# fpga-bank3-outside.net
KiCad netlist of a schematic drawn in Altium Designer
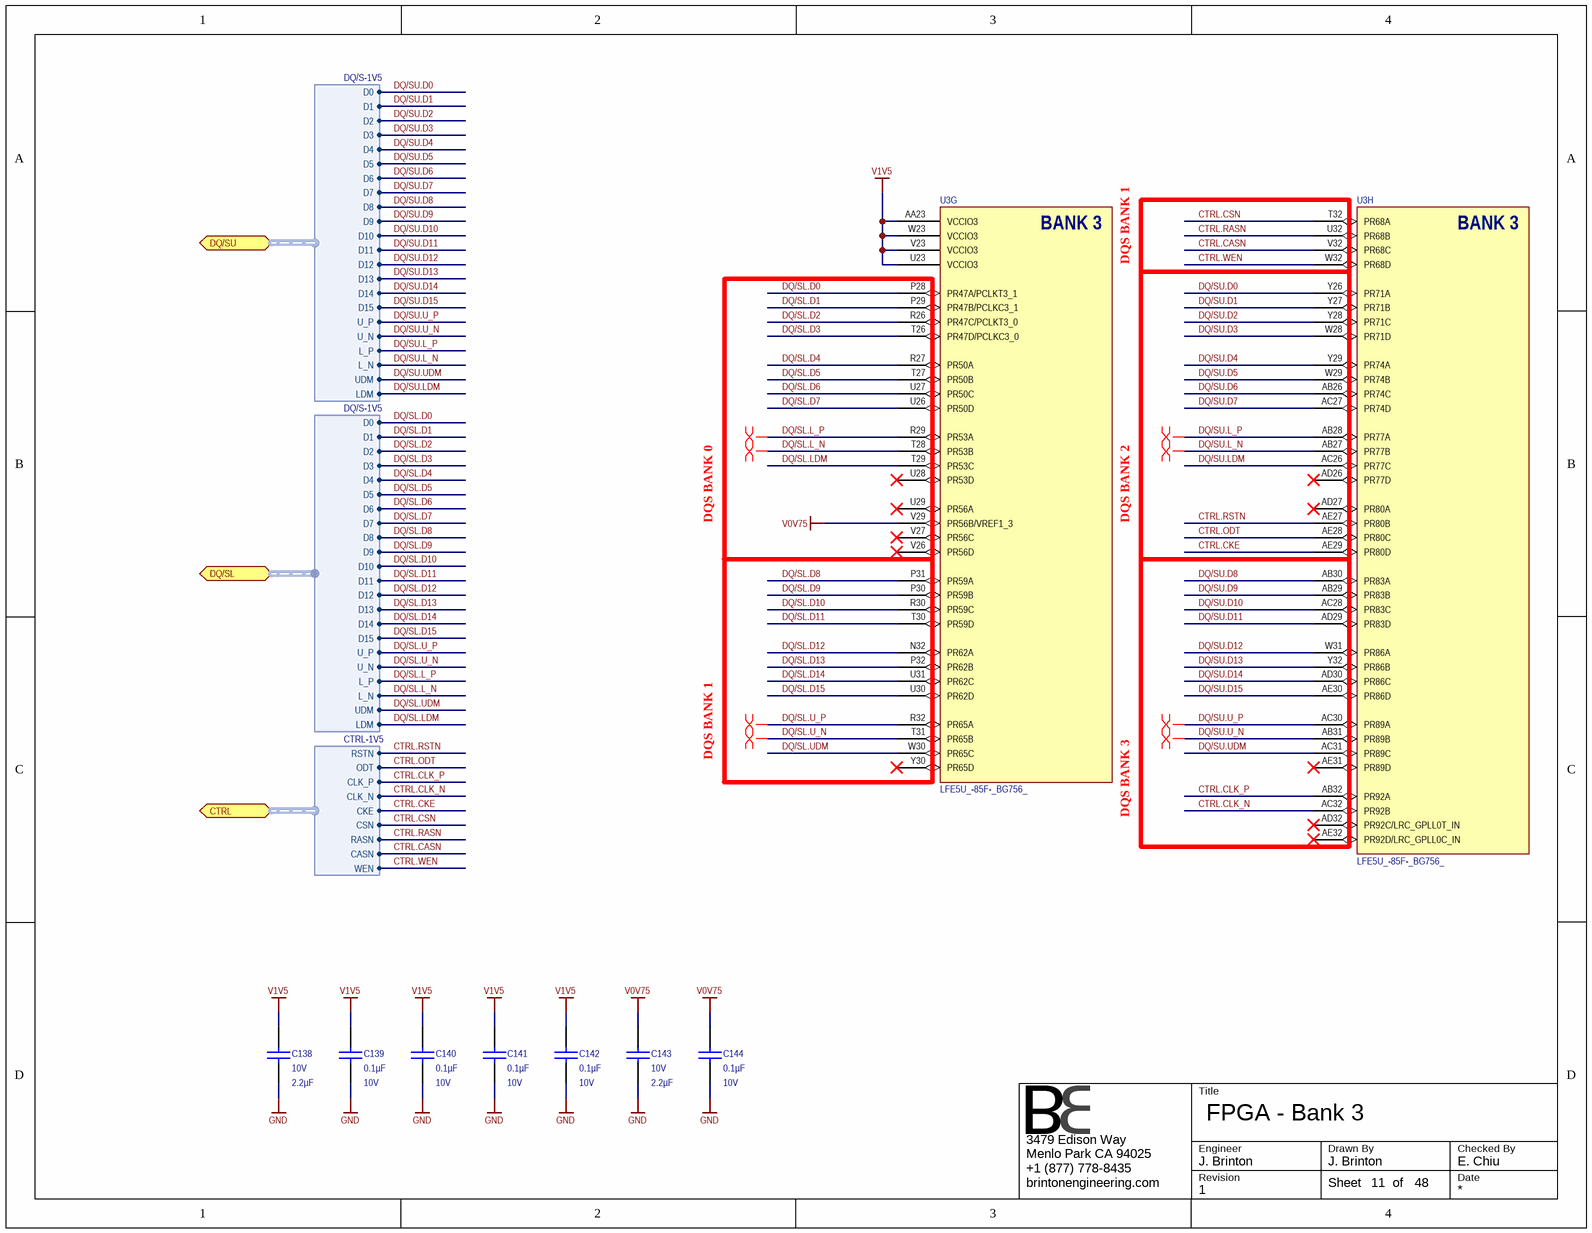
[diagram p0: fpga-bank3-outside.SchDoc]

(export (version "E")
  (design (tool "Eeschema 10.0.6"))
  (components
    (comp (ref "C138")
      (value "GRM188R71A225KE15D")
      (footprint "CAPC1608X90N")
      (description "CAP CER 2.2UF 10V 10% X7R 0603")
      (fields
        (field (name "MANUFACTURER") "Murata Electronics North America")
        (field (name "TOLERANCE") "±10%")
        (field (name "VOLTAGE - RATED") "10V")
        (field (name "CAPACITANCE") "2.2µF")
      )
      (libsource (lib "murata") (part "GRM188R71A225KE15D"))
    )
    (comp (ref "C139")
      (value "GRM155R71A104KA01J")
      (footprint "CAPC1005X56N")
      (description "CAP CER 0.1UF 10V 10% X7R 0402")
      (fields
        (field (name "MANUFACTURER") "Murata Electronics North America")
        (field (name "TOLERANCE") "±10%")
        (field (name "CAPACITANCE") "0.1µF")
        (field (name "VOLTAGE - RATED") "10V")
      )
      (libsource (lib "murata") (part "GRM155R71A104KA01J"))
    )
    (comp (ref "C140")
      (value "GRM155R71A104KA01J")
      (footprint "CAPC1005X56N")
      (description "CAP CER 0.1UF 10V 10% X7R 0402")
      (fields
        (field (name "MANUFACTURER") "Murata Electronics North America")
        (field (name "TOLERANCE") "±10%")
        (field (name "CAPACITANCE") "0.1µF")
        (field (name "VOLTAGE - RATED") "10V")
      )
      (libsource (lib "murata") (part "GRM155R71A104KA01J"))
    )
    (comp (ref "C141")
      (value "GRM155R71A104KA01J")
      (footprint "CAPC1005X56N")
      (description "CAP CER 0.1UF 10V 10% X7R 0402")
      (fields
        (field (name "MANUFACTURER") "Murata Electronics North America")
        (field (name "TOLERANCE") "±10%")
        (field (name "CAPACITANCE") "0.1µF")
        (field (name "VOLTAGE - RATED") "10V")
      )
      (libsource (lib "murata") (part "GRM155R71A104KA01J"))
    )
    (comp (ref "C142")
      (value "GRM155R71A104KA01J")
      (footprint "CAPC1005X56N")
      (description "CAP CER 0.1UF 10V 10% X7R 0402")
      (fields
        (field (name "MANUFACTURER") "Murata Electronics North America")
        (field (name "TOLERANCE") "±10%")
        (field (name "CAPACITANCE") "0.1µF")
        (field (name "VOLTAGE - RATED") "10V")
      )
      (libsource (lib "murata") (part "GRM155R71A104KA01J"))
    )
    (comp (ref "C143")
      (value "GRM188R71A225KE15D")
      (footprint "CAPC1608X90N")
      (description "CAP CER 2.2UF 10V 10% X7R 0603")
      (fields
        (field (name "MANUFACTURER") "Murata Electronics North America")
        (field (name "TOLERANCE") "±10%")
        (field (name "VOLTAGE - RATED") "10V")
        (field (name "CAPACITANCE") "2.2µF")
      )
      (libsource (lib "murata") (part "GRM188R71A225KE15D"))
    )
    (comp (ref "C144")
      (value "GRM155R71A104KA01J")
      (footprint "CAPC1005X56N")
      (description "CAP CER 0.1UF 10V 10% X7R 0402")
      (fields
        (field (name "MANUFACTURER") "Murata Electronics North America")
        (field (name "TOLERANCE") "±10%")
        (field (name "CAPACITANCE") "0.1µF")
        (field (name "VOLTAGE - RATED") "10V")
      )
      (libsource (lib "murata") (part "GRM155R71A104KA01J"))
    )
    (comp (ref "U3")
      (value "LFE5U_-85F-_BG756_")
      (footprint "lattice:caBGA756")
      (description "ECP5 FPGA, 85k LUT, 756-caBGA")
      (fields (field (name "MANUFACTURER") "Lattice Semiconductor"))
      (libsource (lib "lattice") (part "LFE5U_-85F-_BG756_"))
    )
  )
  (nets
    (net (code "3") (name "/CTRL.CASN") (class "Default")
      (node (ref "U3") (pin "V32") (pinfunction "PR68C_V32") (pintype "bidirectional"))
    )
    (net (code "4") (name "/CTRL.CKE") (class "Default")
      (node (ref "U3") (pin "AE29") (pinfunction "PR80D_AE29") (pintype "bidirectional"))
    )
    (net (code "5") (name "/CTRL.CLK_N") (class "Default")
      (node (ref "U3") (pin "AC32") (pinfunction "PR92B_AC32") (pintype "bidirectional"))
    )
    (net (code "6") (name "/CTRL.CLK_P") (class "Default")
      (node (ref "U3") (pin "AB32") (pinfunction "PR92A_AB32") (pintype "bidirectional"))
    )
    (net (code "7") (name "/CTRL.CSN") (class "Default")
      (node (ref "U3") (pin "T32") (pinfunction "PR68A_T32") (pintype "bidirectional"))
    )
    (net (code "8") (name "/CTRL.ODT") (class "Default")
      (node (ref "U3") (pin "AE28") (pinfunction "PR80C_AE28") (pintype "bidirectional"))
    )
    (net (code "9") (name "/CTRL.RASN") (class "Default")
      (node (ref "U3") (pin "U32") (pinfunction "PR68B_U32") (pintype "bidirectional"))
    )
    (net (code "10") (name "/CTRL.RSTN") (class "Default")
      (node (ref "U3") (pin "AE27") (pinfunction "PR80B_AE27") (pintype "bidirectional"))
    )
    (net (code "11") (name "/CTRL.WEN") (class "Default")
      (node (ref "U3") (pin "W32") (pinfunction "PR68D_W32") (pintype "bidirectional"))
    )
    (net (code "12") (name "/DQ{slash}SL.D0") (class "Default")
      (node (ref "U3") (pin "P28") (pinfunction "PR47A/PCLKT3_1_P28") (pintype "bidirectional"))
    )
    (net (code "13") (name "/DQ{slash}SL.D1") (class "Default")
      (node (ref "U3") (pin "P29") (pinfunction "PR47B/PCLKC3_1_P29") (pintype "bidirectional"))
    )
    (net (code "14") (name "/DQ{slash}SL.D2") (class "Default")
      (node (ref "U3") (pin "R26") (pinfunction "PR47C/PCLKT3_0_R26") (pintype "bidirectional"))
    )
    (net (code "15") (name "/DQ{slash}SL.D3") (class "Default")
      (node (ref "U3") (pin "T26") (pinfunction "PR47D/PCLKC3_0_T26") (pintype "bidirectional"))
    )
    (net (code "16") (name "/DQ{slash}SL.D4") (class "Default")
      (node (ref "U3") (pin "R27") (pinfunction "PR50A_R27") (pintype "bidirectional"))
    )
    (net (code "17") (name "/DQ{slash}SL.D5") (class "Default")
      (node (ref "U3") (pin "T27") (pinfunction "PR50B_T27") (pintype "bidirectional"))
    )
    (net (code "18") (name "/DQ{slash}SL.D6") (class "Default")
      (node (ref "U3") (pin "U27") (pinfunction "PR50C_U27") (pintype "bidirectional"))
    )
    (net (code "19") (name "/DQ{slash}SL.D7") (class "Default")
      (node (ref "U3") (pin "U26") (pinfunction "PR50D_U26") (pintype "bidirectional"))
    )
    (net (code "20") (name "/DQ{slash}SL.D8") (class "Default")
      (node (ref "U3") (pin "P31") (pinfunction "PR59A_P31") (pintype "bidirectional"))
    )
    (net (code "21") (name "/DQ{slash}SL.D9") (class "Default")
      (node (ref "U3") (pin "P30") (pinfunction "PR59B_P30") (pintype "bidirectional"))
    )
    (net (code "22") (name "/DQ{slash}SL.D10") (class "Default")
      (node (ref "U3") (pin "R30") (pinfunction "PR59C_R30") (pintype "bidirectional"))
    )
    (net (code "23") (name "/DQ{slash}SL.D11") (class "Default")
      (node (ref "U3") (pin "T30") (pinfunction "PR59D_T30") (pintype "bidirectional"))
    )
    (net (code "24") (name "/DQ{slash}SL.D12") (class "Default")
      (node (ref "U3") (pin "N32") (pinfunction "PR62A_N32") (pintype "bidirectional"))
    )
    (net (code "25") (name "/DQ{slash}SL.D13") (class "Default")
      (node (ref "U3") (pin "P32") (pinfunction "PR62B_P32") (pintype "bidirectional"))
    )
    (net (code "26") (name "/DQ{slash}SL.D14") (class "Default")
      (node (ref "U3") (pin "U31") (pinfunction "PR62C_U31") (pintype "bidirectional"))
    )
    (net (code "27") (name "/DQ{slash}SL.D15") (class "Default")
      (node (ref "U3") (pin "U30") (pinfunction "PR62D_U30") (pintype "bidirectional"))
    )
    (net (code "28") (name "/DQ{slash}SL.LDM") (class "Default")
      (node (ref "U3") (pin "T29") (pinfunction "PR53C_T29") (pintype "bidirectional"))
    )
    (net (code "29") (name "/DQ{slash}SL.L_N") (class "Default")
      (node (ref "U3") (pin "T28") (pinfunction "PR53B_T28") (pintype "bidirectional"))
    )
    (net (code "30") (name "/DQ{slash}SL.L_P") (class "Default")
      (node (ref "U3") (pin "R29") (pinfunction "PR53A_R29") (pintype "bidirectional"))
    )
    (net (code "31") (name "/DQ{slash}SL.UDM") (class "Default")
      (node (ref "U3") (pin "W30") (pinfunction "PR65C_W30") (pintype "bidirectional"))
    )
    (net (code "32") (name "/DQ{slash}SL.U_N") (class "Default")
      (node (ref "U3") (pin "T31") (pinfunction "PR65B_T31") (pintype "bidirectional"))
    )
    (net (code "33") (name "/DQ{slash}SL.U_P") (class "Default")
      (node (ref "U3") (pin "R32") (pinfunction "PR65A_R32") (pintype "bidirectional"))
    )
    (net (code "34") (name "/DQ{slash}SU.D0") (class "Default")
      (node (ref "U3") (pin "Y26") (pinfunction "PR71A_Y26") (pintype "bidirectional"))
    )
    (net (code "35") (name "/DQ{slash}SU.D1") (class "Default")
      (node (ref "U3") (pin "Y27") (pinfunction "PR71B_Y27") (pintype "bidirectional"))
    )
    (net (code "36") (name "/DQ{slash}SU.D2") (class "Default")
      (node (ref "U3") (pin "Y28") (pinfunction "PR71C_Y28") (pintype "bidirectional"))
    )
    (net (code "37") (name "/DQ{slash}SU.D3") (class "Default")
      (node (ref "U3") (pin "W28") (pinfunction "PR71D_W28") (pintype "bidirectional"))
    )
    (net (code "38") (name "/DQ{slash}SU.D4") (class "Default")
      (node (ref "U3") (pin "Y29") (pinfunction "PR74A_Y29") (pintype "bidirectional"))
    )
    (net (code "39") (name "/DQ{slash}SU.D5") (class "Default")
      (node (ref "U3") (pin "W29") (pinfunction "PR74B_W29") (pintype "bidirectional"))
    )
    (net (code "40") (name "/DQ{slash}SU.D6") (class "Default")
      (node (ref "U3") (pin "AB26") (pinfunction "PR74C_AB26") (pintype "bidirectional"))
    )
    (net (code "41") (name "/DQ{slash}SU.D7") (class "Default")
      (node (ref "U3") (pin "AC27") (pinfunction "PR74D_AC27") (pintype "bidirectional"))
    )
    (net (code "42") (name "/DQ{slash}SU.D8") (class "Default")
      (node (ref "U3") (pin "AB30") (pinfunction "PR83A_AB30") (pintype "bidirectional"))
    )
    (net (code "43") (name "/DQ{slash}SU.D9") (class "Default")
      (node (ref "U3") (pin "AB29") (pinfunction "PR83B_AB29") (pintype "bidirectional"))
    )
    (net (code "44") (name "/DQ{slash}SU.D10") (class "Default")
      (node (ref "U3") (pin "AC28") (pinfunction "PR83C_AC28") (pintype "bidirectional"))
    )
    (net (code "45") (name "/DQ{slash}SU.D11") (class "Default")
      (node (ref "U3") (pin "AD29") (pinfunction "PR83D_AD29") (pintype "bidirectional"))
    )
    (net (code "46") (name "/DQ{slash}SU.D12") (class "Default")
      (node (ref "U3") (pin "W31") (pinfunction "PR86A_W31") (pintype "bidirectional"))
    )
    (net (code "47") (name "/DQ{slash}SU.D13") (class "Default")
      (node (ref "U3") (pin "Y32") (pinfunction "PR86B_Y32") (pintype "bidirectional"))
    )
    (net (code "48") (name "/DQ{slash}SU.D14") (class "Default")
      (node (ref "U3") (pin "AD30") (pinfunction "PR86C_AD30") (pintype "bidirectional"))
    )
    (net (code "49") (name "/DQ{slash}SU.D15") (class "Default")
      (node (ref "U3") (pin "AE30") (pinfunction "PR86D_AE30") (pintype "bidirectional"))
    )
    (net (code "50") (name "/DQ{slash}SU.LDM") (class "Default")
      (node (ref "U3") (pin "AC26") (pinfunction "PR77C_AC26") (pintype "bidirectional"))
    )
    (net (code "51") (name "/DQ{slash}SU.L_N") (class "Default")
      (node (ref "U3") (pin "AB27") (pinfunction "PR77B_AB27") (pintype "bidirectional"))
    )
    (net (code "52") (name "/DQ{slash}SU.L_P") (class "Default")
      (node (ref "U3") (pin "AB28") (pinfunction "PR77A_AB28") (pintype "bidirectional"))
    )
    (net (code "53") (name "/DQ{slash}SU.UDM") (class "Default")
      (node (ref "U3") (pin "AC31") (pinfunction "PR89C_AC31") (pintype "bidirectional"))
    )
    (net (code "54") (name "/DQ{slash}SU.U_N") (class "Default")
      (node (ref "U3") (pin "AB31") (pinfunction "PR89B_AB31") (pintype "bidirectional"))
    )
    (net (code "55") (name "/DQ{slash}SU.U_P") (class "Default")
      (node (ref "U3") (pin "AC30") (pinfunction "PR89A_AC30") (pintype "bidirectional"))
    )
    (net (code "58") (name "GND") (class "Default")
      (node (ref "C138") (pin "1") (pinfunction "1_1") (pintype "passive"))
      (node (ref "C139") (pin "1") (pinfunction "1_1") (pintype "passive"))
      (node (ref "C140") (pin "1") (pinfunction "1_1") (pintype "passive"))
      (node (ref "C141") (pin "1") (pinfunction "1_1") (pintype "passive"))
      (node (ref "C142") (pin "1") (pinfunction "1_1") (pintype "passive"))
      (node (ref "C143") (pin "1") (pinfunction "1_1") (pintype "passive"))
      (node (ref "C144") (pin "1") (pinfunction "1_1") (pintype "passive"))
    )
    (net (code "59") (name "V0V75") (class "Default")
      (node (ref "C143") (pin "2") (pinfunction "2_2") (pintype "passive"))
      (node (ref "C144") (pin "2") (pinfunction "2_2") (pintype "passive"))
      (node (ref "U3") (pin "V29") (pinfunction "PR56B/VREF1_3_V29") (pintype "bidirectional"))
    )
    (net (code "60") (name "V1V5") (class "Default")
      (node (ref "C138") (pin "2") (pinfunction "2_2") (pintype "passive"))
      (node (ref "C139") (pin "2") (pinfunction "2_2") (pintype "passive"))
      (node (ref "C140") (pin "2") (pinfunction "2_2") (pintype "passive"))
      (node (ref "C141") (pin "2") (pinfunction "2_2") (pintype "passive"))
      (node (ref "C142") (pin "2") (pinfunction "2_2") (pintype "passive"))
      (node (ref "U3") (pin "AA23") (pinfunction "VCCIO3_AA23") (pintype "power_in"))
      (node (ref "U3") (pin "U23") (pinfunction "VCCIO3_U23") (pintype "power_in"))
      (node (ref "U3") (pin "V23") (pinfunction "VCCIO3_V23") (pintype "power_in"))
      (node (ref "U3") (pin "W23") (pinfunction "VCCIO3_W23") (pintype "power_in"))
    )
    (net (code "61") (name "unconnected-(U3G-PR53D-PadU28)") (class "Default")
      (node (ref "U3") (pin "U28") (pinfunction "PR53D_U28") (pintype "bidirectional+no_connect"))
    )
    (net (code "62") (name "unconnected-(U3G-PR56A-PadU29)") (class "Default")
      (node (ref "U3") (pin "U29") (pinfunction "PR56A_U29") (pintype "bidirectional+no_connect"))
    )
    (net (code "63") (name "unconnected-(U3G-PR56C-PadV27)") (class "Default")
      (node (ref "U3") (pin "V27") (pinfunction "PR56C_V27") (pintype "bidirectional+no_connect"))
    )
    (net (code "64") (name "unconnected-(U3G-PR56D-PadV26)") (class "Default")
      (node (ref "U3") (pin "V26") (pinfunction "PR56D_V26") (pintype "bidirectional+no_connect"))
    )
    (net (code "65") (name "unconnected-(U3G-PR65D-PadY30)") (class "Default")
      (node (ref "U3") (pin "Y30") (pinfunction "PR65D_Y30") (pintype "bidirectional+no_connect"))
    )
    (net (code "66") (name "unconnected-(U3H-PR77D-PadAD26)") (class "Default")
      (node (ref "U3") (pin "AD26") (pinfunction "PR77D_AD26") (pintype "bidirectional+no_connect"))
    )
    (net (code "67") (name "unconnected-(U3H-PR80A-PadAD27)") (class "Default")
      (node (ref "U3") (pin "AD27") (pinfunction "PR80A_AD27") (pintype "bidirectional+no_connect"))
    )
    (net (code "68") (name "unconnected-(U3H-PR89D-PadAE31)") (class "Default")
      (node (ref "U3") (pin "AE31") (pinfunction "PR89D_AE31") (pintype "bidirectional+no_connect"))
    )
    (net (code "69") (name "unconnected-(U3H-PR92C{slash}LRC_GPLL0T_IN-PadAD32)") (class "Default")
      (node (ref "U3") (pin "AD32") (pinfunction "PR92C/LRC_GPLL0T_IN_AD32") (pintype "bidirectional+no_connect"))
    )
    (net (code "70") (name "unconnected-(U3H-PR92D{slash}LRC_GPLL0C_IN-PadAE32)") (class "Default")
      (node (ref "U3") (pin "AE32") (pinfunction "PR92D/LRC_GPLL0C_IN_AE32") (pintype "bidirectional+no_connect"))
    )
  )
)
